# wireless.net
KiCad netlist of a schematic drawn in Altium Designer
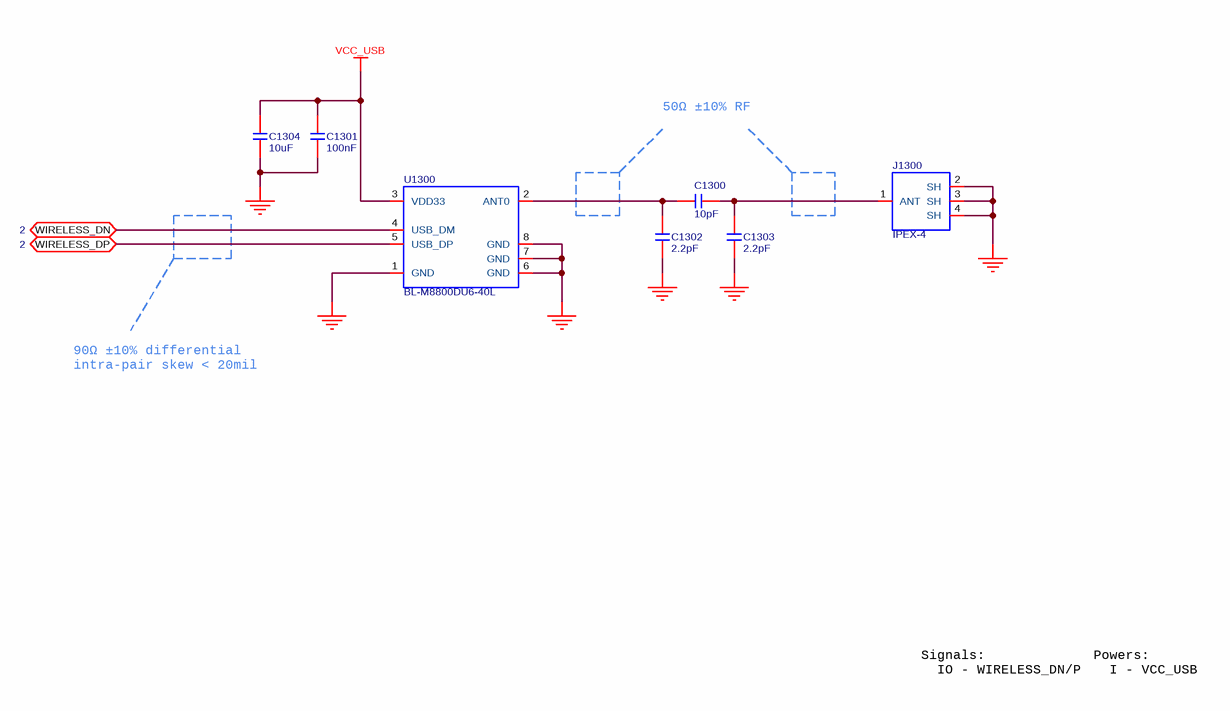
[diagram p0: wireless.schdoc]

(export (version "E")
  (design (tool "Eeschema 10.0.6"))
  (components
    (comp (ref "C1300")
      (value "10pF")
      (footprint "mw:C0201")
      (fields (field (name "VOLTAGE") "25V") (field (name "Comment") "C-NOMO"))
      (libsource (lib "mw") (part "C-NOMO"))
    )
    (comp (ref "C1301")
      (value "100nF")
      (footprint "mw:C0402")
      (fields (field (name "VOLTAGE") "50V") (field (name "Comment") "C-NOMO"))
      (libsource (lib "mw") (part "C-NOMO"))
    )
    (comp (ref "C1302")
      (value "2.2pF")
      (footprint "mw:C0201")
      (fields (field (name "VOLTAGE") "25V") (field (name "Comment") "C-NOMO"))
      (libsource (lib "mw") (part "C-NOMO"))
    )
    (comp (ref "C1303")
      (value "2.2pF")
      (footprint "mw:C0201")
      (fields (field (name "VOLTAGE") "25V") (field (name "Comment") "C-NOMO"))
      (libsource (lib "mw") (part "C-NOMO"))
    )
    (comp (ref "C1304")
      (value "10uF")
      (footprint "mw:C0402")
      (fields (field (name "VOLTAGE") "6.3V") (field (name "Comment") "C-NOMO"))
      (libsource (lib "mw") (part "C-NOMO"))
    )
    (comp (ref "J1300")
      (value "IPEX-4")
      (footprint "mw:IPEX-4")
      (description "SOCKET - RF")
      (libsource (lib "mw") (part "IPEX-4"))
    )
    (comp (ref "U1300")
      (value "BL-M8800DU6-40L")
      (footprint "mw:BL-M8800DU6-40L")
      (description "BTWIFI")
      (libsource (lib "mw") (part "BL-M8800DU6-40L"))
    )
  )
  (nets
    (net (code "1") (name "/WIRELESS_DN") (class "Default")
      (node (ref "U1300") (pin "4") (pinfunction "USB_DM_4") (pintype "passive"))
    )
    (net (code "2") (name "/WIRELESS_DP") (class "Default")
      (node (ref "U1300") (pin "5") (pinfunction "USB_DP_5") (pintype "passive"))
    )
    (net (code "3") (name "GND") (class "Default")
      (node (ref "C1301") (pin "2") (pinfunction "2_2") (pintype "passive"))
      (node (ref "C1302") (pin "2") (pinfunction "2_2") (pintype "passive"))
      (node (ref "C1303") (pin "2") (pinfunction "2_2") (pintype "passive"))
      (node (ref "C1304") (pin "1") (pinfunction "1_1") (pintype "passive"))
      (node (ref "J1300") (pin "2") (pinfunction "SH_2") (pintype "passive"))
      (node (ref "J1300") (pin "3") (pinfunction "SH_3") (pintype "passive"))
      (node (ref "J1300") (pin "4") (pinfunction "SH_4") (pintype "passive"))
      (node (ref "U1300") (pin "1") (pinfunction "GND_1") (pintype "passive"))
      (node (ref "U1300") (pin "6") (pinfunction "GND_6") (pintype "passive"))
      (node (ref "U1300") (pin "7") (pinfunction "GND_7") (pintype "passive"))
      (node (ref "U1300") (pin "8") (pinfunction "GND_8") (pintype "passive"))
    )
    (net (code "4") (name "Net-(J1300-ANT)") (class "Default")
      (node (ref "C1300") (pin "1") (pinfunction "1_1") (pintype "passive"))
      (node (ref "C1303") (pin "1") (pinfunction "1_1") (pintype "passive"))
      (node (ref "J1300") (pin "1") (pinfunction "ANT_1") (pintype "passive"))
    )
    (net (code "5") (name "Net-(U1300-ANT0)") (class "Default")
      (node (ref "C1300") (pin "2") (pinfunction "2_2") (pintype "passive"))
      (node (ref "C1302") (pin "1") (pinfunction "1_1") (pintype "passive"))
      (node (ref "U1300") (pin "2") (pinfunction "ANT0_2") (pintype "passive"))
    )
    (net (code "6") (name "VCC_USB") (class "Default")
      (node (ref "C1301") (pin "1") (pinfunction "1_1") (pintype "passive"))
      (node (ref "C1304") (pin "2") (pinfunction "2_2") (pintype "passive"))
      (node (ref "U1300") (pin "3") (pinfunction "VDD33_3") (pintype "passive"))
    )
  )
)
